# RGMII_ETH_PHY.net
KiCad netlist of a schematic drawn in Altium Designer
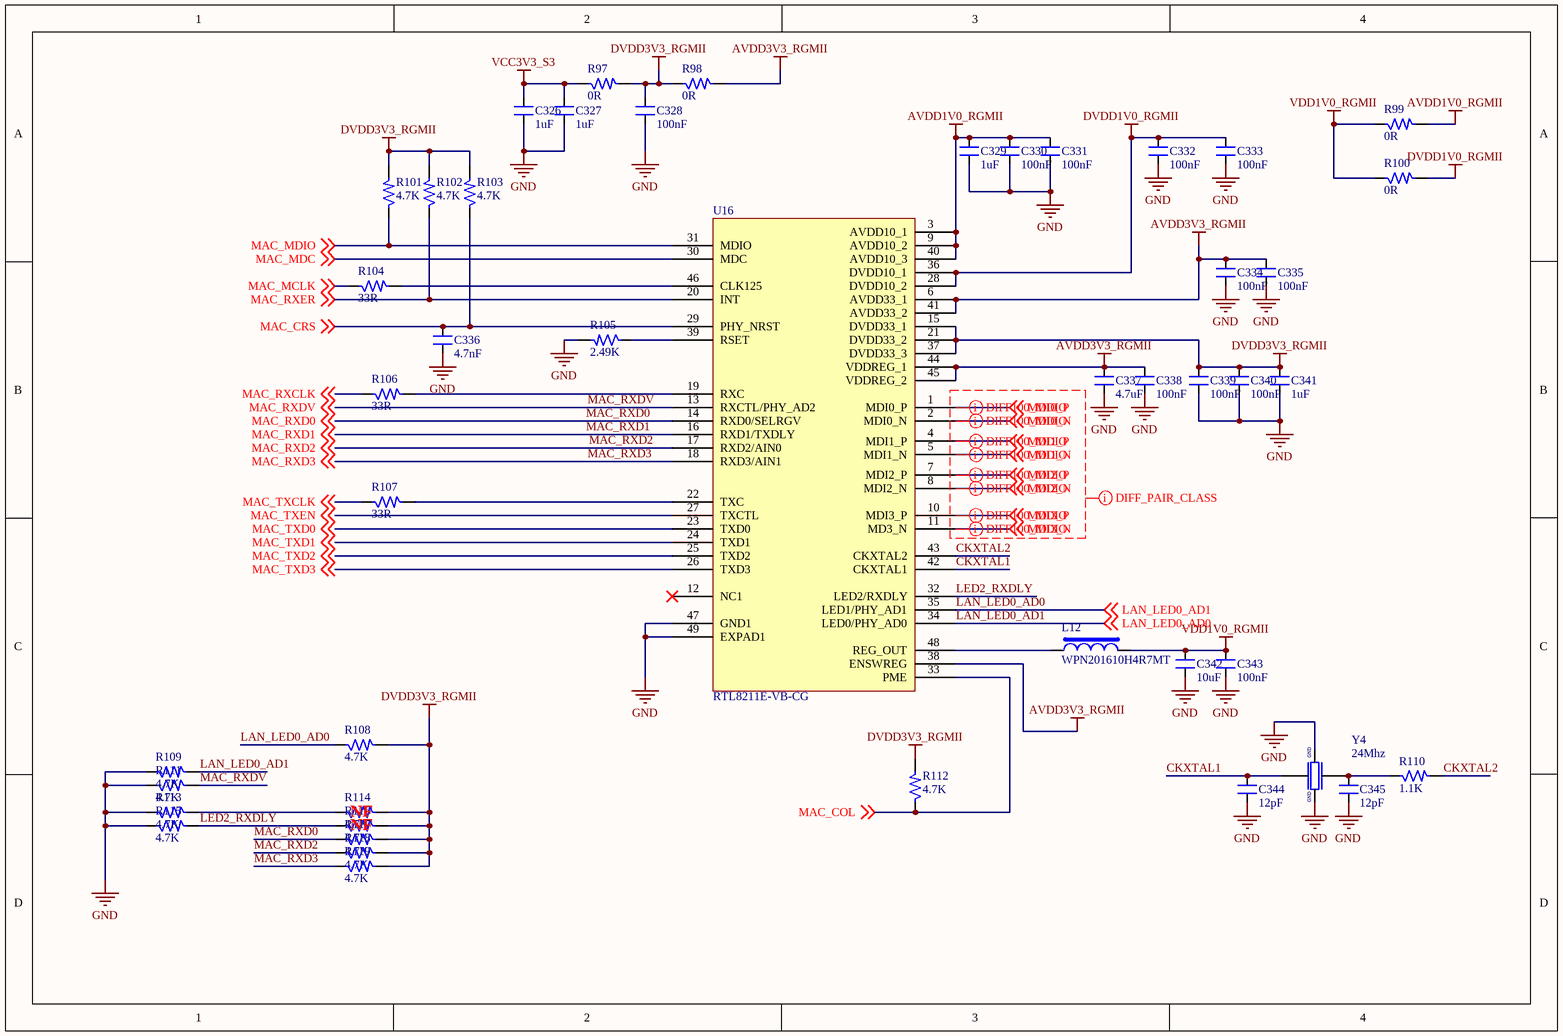
[diagram p0: RGMII ETH PHY.SchDoc]

(export (version "E")
  (design (tool "Eeschema 10.0.6"))
  (components
    (comp (ref "C326")
      (value "1uF")
      (footprint "CAP_0603")
      (description "1µF ±10% 10V Ceramic Capacitor X5R 0603 (1608 Metric)")
      (fields
        (field (name "MANUFACTURER") "Samsung Electro-Mechanics")
        (field (name "MANUFACTURER PART NUMBER") "CL10A105KP8NNNC")
      )
      (libsource (lib "RK3399 _Module_Schlib") (part "CAP_1uF-10V-5%-0603"))
    )
    (comp (ref "C327")
      (value "1uF")
      (footprint "CAP_0603")
      (description "1µF ±10% 10V Ceramic Capacitor X5R 0603 (1608 Metric)")
      (fields
        (field (name "MANUFACTURER") "Samsung Electro-Mechanics")
        (field (name "MANUFACTURER PART NUMBER") "CL10A105KP8NNNC")
      )
      (libsource (lib "RK3399 _Module_Schlib") (part "CAP_1uF-10V-5%-0603"))
    )
    (comp (ref "C328")
      (value "100nF")
      (footprint "CAP_0603")
      (description "0.1µF ±10% 10V Ceramic Capacitor X7R 0603 (1608 Metric)")
      (fields
        (field (name "MANUFACTURER") "Yageo")
        (field (name "MANUFACTURER PART NUMBER") "CC0603KRX7R6BB104")
      )
      (libsource (lib "RK3399 _Module_Schlib") (part "CAP_100nF-10V-5%-0603"))
    )
    (comp (ref "C329")
      (value "1uF")
      (footprint "CAP_0603")
      (description "1µF ±10% 10V Ceramic Capacitor X5R 0603 (1608 Metric)")
      (fields
        (field (name "MANUFACTURER") "Samsung Electro-Mechanics")
        (field (name "MANUFACTURER PART NUMBER") "CL10A105KP8NNNC")
      )
      (libsource (lib "RK3399 _Module_Schlib") (part "CAP_1uF-10V-5%-0603"))
    )
    (comp (ref "C330")
      (value "100nF")
      (footprint "CAP_0603")
      (description "0.1µF ±10% 10V Ceramic Capacitor X7R 0603 (1608 Metric)")
      (fields
        (field (name "MANUFACTURER") "Yageo")
        (field (name "MANUFACTURER PART NUMBER") "CC0603KRX7R6BB104")
      )
      (libsource (lib "RK3399 _Module_Schlib") (part "CAP_100nF-10V-5%-0603"))
    )
    (comp (ref "C331")
      (value "100nF")
      (footprint "CAP_0603")
      (description "0.1µF ±10% 10V Ceramic Capacitor X7R 0603 (1608 Metric)")
      (fields
        (field (name "MANUFACTURER") "Yageo")
        (field (name "MANUFACTURER PART NUMBER") "CC0603KRX7R6BB104")
      )
      (libsource (lib "RK3399 _Module_Schlib") (part "CAP_100nF-10V-5%-0603"))
    )
    (comp (ref "C332")
      (value "100nF")
      (footprint "CAP_0603")
      (description "0.1µF ±10% 10V Ceramic Capacitor X7R 0603 (1608 Metric)")
      (fields
        (field (name "MANUFACTURER") "Yageo")
        (field (name "MANUFACTURER PART NUMBER") "CC0603KRX7R6BB104")
      )
      (libsource (lib "RK3399 _Module_Schlib") (part "CAP_100nF-10V-5%-0603"))
    )
    (comp (ref "C333")
      (value "100nF")
      (footprint "CAP_0603")
      (description "0.1µF ±10% 10V Ceramic Capacitor X7R 0603 (1608 Metric)")
      (fields
        (field (name "MANUFACTURER") "Yageo")
        (field (name "MANUFACTURER PART NUMBER") "CC0603KRX7R6BB104")
      )
      (libsource (lib "RK3399 _Module_Schlib") (part "CAP_100nF-10V-5%-0603"))
    )
    (comp (ref "C334")
      (value "100nF")
      (footprint "CAP_0603")
      (description "0.1µF ±10% 10V Ceramic Capacitor X7R 0603 (1608 Metric)")
      (fields
        (field (name "MANUFACTURER") "Yageo")
        (field (name "MANUFACTURER PART NUMBER") "CC0603KRX7R6BB104")
      )
      (libsource (lib "RK3399 _Module_Schlib") (part "CAP_100nF-10V-5%-0603"))
    )
    (comp (ref "C335")
      (value "100nF")
      (footprint "CAP_0603")
      (description "0.1µF ±10% 10V Ceramic Capacitor X7R 0603 (1608 Metric)")
      (fields
        (field (name "MANUFACTURER") "Yageo")
        (field (name "MANUFACTURER PART NUMBER") "CC0603KRX7R6BB104")
      )
      (libsource (lib "RK3399 _Module_Schlib") (part "CAP_100nF-10V-5%-0603"))
    )
    (comp (ref "C336")
      (value "4.7nF")
      (footprint "CAP_0603")
      (description "4700pF ±10% 10V Ceramic Capacitor X7R 0603 (1608 Metric)")
      (fields
        (field (name "MANUFACTURER") "KEMET")
        (field (name "MANUFACTURER PART NUMBER") "C0603C472K8RACTU")
      )
      (libsource (lib "RK3399 _Module_Schlib") (part "CAP_4.7nF-10V-10%-0603"))
    )
    (comp (ref "C337")
      (value "4.7uF")
      (footprint "CAP_0603")
      (description "4.7µF ±10% 16V Ceramic Capacitor X5R 0603 (1608 Metric)")
      (fields
        (field (name "MANUFACTURER") "Murata Electronics")
        (field (name "MANUFACTURER PART NUMBER") "GRM188R61C475KAAJD")
      )
      (libsource (lib "RK3399 _Module_Schlib") (part "CAP_4.7uF-16V-10%-0603"))
    )
    (comp (ref "C338")
      (value "100nF")
      (footprint "CAP_0603")
      (description "0.1µF ±10% 10V Ceramic Capacitor X7R 0603 (1608 Metric)")
      (fields
        (field (name "MANUFACTURER") "Yageo")
        (field (name "MANUFACTURER PART NUMBER") "CC0603KRX7R6BB104")
      )
      (libsource (lib "RK3399 _Module_Schlib") (part "CAP_100nF-10V-5%-0603"))
    )
    (comp (ref "C339")
      (value "100nF")
      (footprint "CAP_0603")
      (description "0.1µF ±10% 10V Ceramic Capacitor X7R 0603 (1608 Metric)")
      (fields
        (field (name "MANUFACTURER") "Yageo")
        (field (name "MANUFACTURER PART NUMBER") "CC0603KRX7R6BB104")
      )
      (libsource (lib "RK3399 _Module_Schlib") (part "CAP_100nF-10V-5%-0603"))
    )
    (comp (ref "C340")
      (value "100nF")
      (footprint "CAP_0603")
      (description "0.1µF ±10% 10V Ceramic Capacitor X7R 0603 (1608 Metric)")
      (fields
        (field (name "MANUFACTURER") "Yageo")
        (field (name "MANUFACTURER PART NUMBER") "CC0603KRX7R6BB104")
      )
      (libsource (lib "RK3399 _Module_Schlib") (part "CAP_100nF-10V-5%-0603"))
    )
    (comp (ref "C341")
      (value "1uF")
      (footprint "CAP_0603")
      (description "1µF ±10% 10V Ceramic Capacitor X5R 0603 (1608 Metric)")
      (fields
        (field (name "MANUFACTURER") "Samsung Electro-Mechanics")
        (field (name "MANUFACTURER PART NUMBER") "CL10A105KP8NNNC")
      )
      (libsource (lib "RK3399 _Module_Schlib") (part "CAP_1uF-10V-5%-0603"))
    )
    (comp (ref "C342")
      (value "10uF")
      (footprint "CAP_0603")
      (description "10µF ±10% 10V Ceramic Capacitor X5R 0603 (1608 Metric)")
      (fields
        (field (name "MANUFACTURER PART NUMBER") "GRM188R61A106KE69J")
        (field (name "MANUFACTURER") "Murata Electronics")
      )
      (libsource (lib "RK3399 _Module_Schlib") (part "CAP_10uF-10V-10%-0603"))
    )
    (comp (ref "C343")
      (value "100nF")
      (footprint "CAP_0603")
      (description "0.1µF ±10% 10V Ceramic Capacitor X7R 0603 (1608 Metric)")
      (fields
        (field (name "MANUFACTURER") "Yageo")
        (field (name "MANUFACTURER PART NUMBER") "CC0603KRX7R6BB104")
      )
      (libsource (lib "RK3399 _Module_Schlib") (part "CAP_100nF-10V-5%-0603"))
    )
    (comp (ref "C344")
      (value "12pF")
      (footprint "CAP_0603")
      (description "12pF ±10% 10V Ceramic Capacitor X8R 0603 (1608 Metric)")
      (fields
        (field (name "MANUFACTURER") "KEMET")
        (field (name "MANUFACTURER PART NUMBER") "C0603X120K8HAC7867")
      )
      (libsource (lib "RK3399 _Module_Schlib") (part "CAP_12pF-10V-10%-0603"))
    )
    (comp (ref "C345")
      (value "12pF")
      (footprint "CAP_0603")
      (description "12pF ±10% 10V Ceramic Capacitor X8R 0603 (1608 Metric)")
      (fields
        (field (name "MANUFACTURER") "KEMET")
        (field (name "MANUFACTURER PART NUMBER") "C0603X120K8HAC7867")
      )
      (libsource (lib "RK3399 _Module_Schlib") (part "CAP_12pF-10V-10%-0603"))
    )
    (comp (ref "L12")
      (value "WPN201610H4R7MT")
      (footprint "IND_62.9_110X86.6_SMD")
      (description "4.7uH ±20% 900mA 425mΩ SMD,2.0x1.6x1.0mm Power Inductors RoHS")
      (fields (field (name "MANUFACTURER") "Sunlord"))
      (libsource (lib "RK3399 _Module_Schlib") (part "IND_4.7uH-0.9A-20%-SMD"))
    )
    (comp (ref "R97")
      (value "0R")
      (footprint "RES_0603")
      (description "0 Ohms Jumper 0.1W, 1/10W Chip Resistor 0603 (1608 Metric) Thick Film")
      (fields
        (field (name "MANUFACTURER") "Yageo")
        (field (name "MANUFACTURER PART NUMBER") "RC0603JR-070RL")
      )
      (libsource (lib "RK3399 _Module_Schlib") (part "RES_0R-0.1W-1%-0603"))
    )
    (comp (ref "R98")
      (value "0R")
      (footprint "RES_0603")
      (description "0 Ohms Jumper 0.1W, 1/10W Chip Resistor 0603 (1608 Metric) Thick Film")
      (fields
        (field (name "MANUFACTURER") "Yageo")
        (field (name "MANUFACTURER PART NUMBER") "RC0603JR-070RL")
      )
      (libsource (lib "RK3399 _Module_Schlib") (part "RES_0R-0.1W-1%-0603"))
    )
    (comp (ref "R99")
      (value "0R")
      (footprint "RES_0603")
      (description "0 Ohms Jumper 0.1W, 1/10W Chip Resistor 0603 (1608 Metric) Thick Film")
      (fields
        (field (name "MANUFACTURER") "Yageo")
        (field (name "MANUFACTURER PART NUMBER") "RC0603JR-070RL")
      )
      (libsource (lib "RK3399 _Module_Schlib") (part "RES_0R-0.1W-1%-0603"))
    )
    (comp (ref "R100")
      (value "0R")
      (footprint "RES_0603")
      (description "0 Ohms Jumper 0.1W, 1/10W Chip Resistor 0603 (1608 Metric) Thick Film")
      (fields
        (field (name "MANUFACTURER") "Yageo")
        (field (name "MANUFACTURER PART NUMBER") "RC0603JR-070RL")
      )
      (libsource (lib "RK3399 _Module_Schlib") (part "RES_0R-0.1W-1%-0603"))
    )
    (comp (ref "R101")
      (value "4.7K")
      (footprint "RES_0603")
      (fields
        (field (name "MANUFACTURER") "TE Connectivity Passive Product")
        (field (name "MANUFACTURER PART NUMBER") "CRGCQ0603F4K7")
      )
      (libsource (lib "RK3399 _Module_Schlib") (part "RES_4.7K-0.1W-1%-0603"))
    )
    (comp (ref "R102")
      (value "4.7K")
      (footprint "RES_0603")
      (fields
        (field (name "MANUFACTURER") "TE Connectivity Passive Product")
        (field (name "MANUFACTURER PART NUMBER") "CRGCQ0603F4K7")
      )
      (libsource (lib "RK3399 _Module_Schlib") (part "RES_4.7K-0.1W-1%-0603"))
    )
    (comp (ref "R103")
      (value "4.7K")
      (footprint "RES_0603")
      (fields
        (field (name "MANUFACTURER") "TE Connectivity Passive Product")
        (field (name "MANUFACTURER PART NUMBER") "CRGCQ0603F4K7")
      )
      (libsource (lib "RK3399 _Module_Schlib") (part "RES_4.7K-0.1W-1%-0603"))
    )
    (comp (ref "R104")
      (value "33R")
      (footprint "RES_0402")
      (description "33 Ohms ±1% 0.1W, 1/10W Chip Resistor 0402 (1005 Metric) Automotive AEC-Q200 Thick Film")
      (fields
        (field (name "MANUFACTURER") "Panasonic Electronic Components")
        (field (name "MANUFACTURER PART NUMBER") "ERJ-2RKF33R0X")
      )
      (libsource (lib "RK3399 _Module_Schlib") (part "RES_33R-0.1W-1%-0402"))
    )
    (comp (ref "R105")
      (value "2.49K")
      (footprint "RES_0603")
      (description "2.49 kOhms ±1% 0.1W, 1/10W Chip Resistor 0603 (1608 Metric) Automotive AEC-Q200 Thick Film")
      (fields
        (field (name "MANUFACTURER") "Stackpole Electronics Inc")
        (field (name "MANUFACTURER PART NUMBER") "RMCF0603FT2K49")
      )
      (libsource (lib "RK3399 _Module_Schlib") (part "RES_2.49K-0.1W-1%-0603"))
    )
    (comp (ref "R106")
      (value "33R")
      (footprint "RES_0402")
      (description "33 Ohms ±1% 0.1W, 1/10W Chip Resistor 0402 (1005 Metric) Automotive AEC-Q200 Thick Film")
      (fields
        (field (name "MANUFACTURER") "Panasonic Electronic Components")
        (field (name "MANUFACTURER PART NUMBER") "ERJ-2RKF33R0X")
      )
      (libsource (lib "RK3399 _Module_Schlib") (part "RES_33R-0.1W-1%-0402"))
    )
    (comp (ref "R107")
      (value "33R")
      (footprint "RES_0402")
      (description "33 Ohms ±1% 0.1W, 1/10W Chip Resistor 0402 (1005 Metric) Automotive AEC-Q200 Thick Film")
      (fields
        (field (name "MANUFACTURER") "Panasonic Electronic Components")
        (field (name "MANUFACTURER PART NUMBER") "ERJ-2RKF33R0X")
      )
      (libsource (lib "RK3399 _Module_Schlib") (part "RES_33R-0.1W-1%-0402"))
    )
    (comp (ref "R108")
      (value "4.7K")
      (footprint "RES_0603")
      (fields
        (field (name "MANUFACTURER") "TE Connectivity Passive Product")
        (field (name "MANUFACTURER PART NUMBER") "CRGCQ0603F4K7")
      )
      (libsource (lib "RK3399 _Module_Schlib") (part "RES_4.7K-0.1W-1%-0603"))
    )
    (comp (ref "R109")
      (value "4.7K")
      (footprint "RES_0603")
      (fields
        (field (name "MANUFACTURER") "TE Connectivity Passive Product")
        (field (name "MANUFACTURER PART NUMBER") "CRGCQ0603F4K7")
      )
      (libsource (lib "RK3399 _Module_Schlib") (part "RES_4.7K-0.1W-1%-0603"))
    )
    (comp (ref "R110")
      (value "1.1K")
      (footprint "RES_0603")
      (description "47 kOhms ±1% 0.1W, 1/10W Chip Resistor 0603 (1608 Metric) Thick Film")
      (fields
        (field (name "MANUFACTURER") "Yageo")
        (field (name "MANUFACTURER PART NUMBER") "RC0603FR-0747KL")
      )
      (libsource (lib "RK3399 _Module_Schlib") (part "RES_1.1K-0.1W-1%-0603"))
    )
    (comp (ref "R111")
      (value "4.7K")
      (footprint "RES_0603")
      (fields
        (field (name "MANUFACTURER") "TE Connectivity Passive Product")
        (field (name "MANUFACTURER PART NUMBER") "CRGCQ0603F4K7")
      )
      (libsource (lib "RK3399 _Module_Schlib") (part "RES_4.7K-0.1W-1%-0603"))
    )
    (comp (ref "R112")
      (value "4.7K")
      (footprint "RES_0603")
      (fields
        (field (name "MANUFACTURER") "TE Connectivity Passive Product")
        (field (name "MANUFACTURER PART NUMBER") "CRGCQ0603F4K7")
      )
      (libsource (lib "RK3399 _Module_Schlib") (part "RES_4.7K-0.1W-1%-0603"))
    )
    (comp (ref "R113")
      (value "4.7K")
      (footprint "RES_0603")
      (fields
        (field (name "MANUFACTURER") "TE Connectivity Passive Product")
        (field (name "MANUFACTURER PART NUMBER") "CRGCQ0603F4K7")
      )
      (libsource (lib "RK3399 _Module_Schlib") (part "RES_4.7K-0.1W-1%-0603"))
    )
    (comp (ref "R114")
      (value "4.7K")
      (footprint "RES_0603")
      (fields
        (field (name "MANUFACTURER") "TE Connectivity Passive Product")
        (field (name "MANUFACTURER PART NUMBER") "CRGCQ0603F4K7")
      )
      (libsource (lib "RK3399 _Module_Schlib") (part "RES_4.7K-0.1W-1%-0603"))
    )
    (comp (ref "R115")
      (value "4.7K")
      (footprint "RES_0603")
      (fields
        (field (name "MANUFACTURER") "TE Connectivity Passive Product")
        (field (name "MANUFACTURER PART NUMBER") "CRGCQ0603F4K7")
      )
      (libsource (lib "RK3399 _Module_Schlib") (part "RES_4.7K-0.1W-1%-0603"))
    )
    (comp (ref "R116")
      (value "4.7K")
      (footprint "RES_0603")
      (fields
        (field (name "MANUFACTURER") "TE Connectivity Passive Product")
        (field (name "MANUFACTURER PART NUMBER") "CRGCQ0603F4K7")
      )
      (libsource (lib "RK3399 _Module_Schlib") (part "RES_4.7K-0.1W-1%-0603"))
    )
    (comp (ref "R117")
      (value "4.7K")
      (footprint "RES_0603")
      (fields
        (field (name "MANUFACTURER") "TE Connectivity Passive Product")
        (field (name "MANUFACTURER PART NUMBER") "CRGCQ0603F4K7")
      )
      (libsource (lib "RK3399 _Module_Schlib") (part "RES_4.7K-0.1W-1%-0603"))
    )
    (comp (ref "R118")
      (value "4.7K")
      (footprint "RES_0603")
      (fields
        (field (name "MANUFACTURER") "TE Connectivity Passive Product")
        (field (name "MANUFACTURER PART NUMBER") "CRGCQ0603F4K7")
      )
      (libsource (lib "RK3399 _Module_Schlib") (part "RES_4.7K-0.1W-1%-0603"))
    )
    (comp (ref "R119")
      (value "4.7K")
      (footprint "RES_0603")
      (fields
        (field (name "MANUFACTURER") "TE Connectivity Passive Product")
        (field (name "MANUFACTURER PART NUMBER") "CRGCQ0603F4K7")
      )
      (libsource (lib "RK3399 _Module_Schlib") (part "RES_4.7K-0.1W-1%-0603"))
    )
    (comp (ref "U16")
      (value "RTL8211E-VB-CG")
      (footprint "QFN48_19.6_324X324_SMD")
      (fields (field (name "MANUFACTURER") "Realtek Semicon"))
      (libsource (lib "RK3399 _Module_Schlib") (part "IC_RTL8211E-VB-CG"))
    )
    (comp (ref "Y4")
      (value "24Mhz")
      (footprint "XTAL_ABM8AIG-24.000MHZ-12-2Z-T3")
      (description "24MHz ±20ppm Crystal 12pF 50 Ohms 4-SMD, No Lead")
      (fields
        (field (name "MANUFACTURER") "Abracon LLC")
        (field (name "MANUFACTURER PART NUMBER") "ABM8AIG-24.000MHZ-12-2Z-T3")
      )
      (libsource (lib "RK3399 _Module_Schlib") (part "XTAL_24Mhz-12pF-4-SMD"))
    )
  )
  (nets
    (net (code "1") (name "/CKXTAL1") (class "Default")
      (node (ref "C344") (pin "2") (pinfunction "2_2") (pintype "passive"))
      (node (ref "U16") (pin "42") (pinfunction "CKXTAL1_42") (pintype "passive"))
      (node (ref "Y4") (pin "1") (pinfunction "1_1") (pintype "passive"))
    )
    (net (code "2") (name "/CKXTAL2") (class "Default")
      (node (ref "R110") (pin "2") (pinfunction "2_2") (pintype "passive"))
      (node (ref "U16") (pin "43") (pinfunction "CKXTAL2_43") (pintype "passive"))
    )
    (net (code "3") (name "/LED2_RXDLY") (class "Default")
      (node (ref "R115") (pin "2") (pinfunction "2_2") (pintype "passive"))
      (node (ref "R116") (pin "1") (pinfunction "1_1") (pintype "passive"))
      (node (ref "U16") (pin "32") (pinfunction "LED2/RXDLY_32") (pintype "passive"))
    )
    (net (code "4") (name "AVDD1V0_RGMII") (class "Default")
      (node (ref "C329") (pin "2") (pinfunction "2_2") (pintype "passive"))
      (node (ref "C330") (pin "2") (pinfunction "2_2") (pintype "passive"))
      (node (ref "C331") (pin "2") (pinfunction "2_2") (pintype "passive"))
      (node (ref "R99") (pin "2") (pinfunction "2_2") (pintype "passive"))
      (node (ref "U16") (pin "3") (pinfunction "AVDD10_1_3") (pintype "passive"))
      (node (ref "U16") (pin "40") (pinfunction "AVDD10_3_40") (pintype "passive"))
      (node (ref "U16") (pin "9") (pinfunction "AVDD10_2_9") (pintype "passive"))
    )
    (net (code "5") (name "AVDD3V3_RGMII") (class "Default")
      (node (ref "C334") (pin "2") (pinfunction "2_2") (pintype "passive"))
      (node (ref "C335") (pin "2") (pinfunction "2_2") (pintype "passive"))
      (node (ref "C337") (pin "2") (pinfunction "2_2") (pintype "passive"))
      (node (ref "C338") (pin "2") (pinfunction "2_2") (pintype "passive"))
      (node (ref "R98") (pin "2") (pinfunction "2_2") (pintype "passive"))
      (node (ref "U16") (pin "38") (pinfunction "ENSWREG_38") (pintype "passive"))
      (node (ref "U16") (pin "41") (pinfunction "AVDD33_2_41") (pintype "passive"))
      (node (ref "U16") (pin "44") (pinfunction "VDDREG_1_44") (pintype "passive"))
      (node (ref "U16") (pin "45") (pinfunction "VDDREG_2_45") (pintype "passive"))
      (node (ref "U16") (pin "6") (pinfunction "AVDD33_1_6") (pintype "passive"))
    )
    (net (code "6") (name "DVDD1V0_RGMII") (class "Default")
      (node (ref "C332") (pin "2") (pinfunction "2_2") (pintype "passive"))
      (node (ref "C333") (pin "2") (pinfunction "2_2") (pintype "passive"))
      (node (ref "R100") (pin "2") (pinfunction "2_2") (pintype "passive"))
      (node (ref "U16") (pin "28") (pinfunction "DVDD10_2_28") (pintype "passive"))
      (node (ref "U16") (pin "36") (pinfunction "DVDD10_1_36") (pintype "passive"))
    )
    (net (code "7") (name "DVDD3V3_RGMII") (class "Default")
      (node (ref "C328") (pin "2") (pinfunction "2_2") (pintype "passive"))
      (node (ref "C339") (pin "2") (pinfunction "2_2") (pintype "passive"))
      (node (ref "C340") (pin "2") (pinfunction "2_2") (pintype "passive"))
      (node (ref "C341") (pin "2") (pinfunction "2_2") (pintype "passive"))
      (node (ref "R101") (pin "2") (pinfunction "2_2") (pintype "passive"))
      (node (ref "R102") (pin "2") (pinfunction "2_2") (pintype "passive"))
      (node (ref "R103") (pin "2") (pinfunction "2_2") (pintype "passive"))
      (node (ref "R108") (pin "2") (pinfunction "2_2") (pintype "passive"))
      (node (ref "R112") (pin "2") (pinfunction "2_2") (pintype "passive"))
      (node (ref "R114") (pin "2") (pinfunction "2_2") (pintype "passive"))
      (node (ref "R116") (pin "2") (pinfunction "2_2") (pintype "passive"))
      (node (ref "R117") (pin "2") (pinfunction "2_2") (pintype "passive"))
      (node (ref "R118") (pin "2") (pinfunction "2_2") (pintype "passive"))
      (node (ref "R119") (pin "2") (pinfunction "2_2") (pintype "passive"))
      (node (ref "R97") (pin "2") (pinfunction "2_2") (pintype "passive"))
      (node (ref "R98") (pin "1") (pinfunction "1_1") (pintype "passive"))
      (node (ref "U16") (pin "15") (pinfunction "DVDD33_1_15") (pintype "passive"))
      (node (ref "U16") (pin "21") (pinfunction "DVDD33_2_21") (pintype "passive"))
      (node (ref "U16") (pin "37") (pinfunction "DVDD33_3_37") (pintype "passive"))
    )
    (net (code "8") (name "GND") (class "Default")
      (node (ref "C326") (pin "1") (pinfunction "1_1") (pintype "passive"))
      (node (ref "C327") (pin "1") (pinfunction "1_1") (pintype "passive"))
      (node (ref "C328") (pin "1") (pinfunction "1_1") (pintype "passive"))
      (node (ref "C329") (pin "1") (pinfunction "1_1") (pintype "passive"))
      (node (ref "C330") (pin "1") (pinfunction "1_1") (pintype "passive"))
      (node (ref "C331") (pin "1") (pinfunction "1_1") (pintype "passive"))
      (node (ref "C332") (pin "1") (pinfunction "1_1") (pintype "passive"))
      (node (ref "C333") (pin "1") (pinfunction "1_1") (pintype "passive"))
      (node (ref "C334") (pin "1") (pinfunction "1_1") (pintype "passive"))
      (node (ref "C335") (pin "1") (pinfunction "1_1") (pintype "passive"))
      (node (ref "C336") (pin "1") (pinfunction "1_1") (pintype "passive"))
      (node (ref "C337") (pin "1") (pinfunction "1_1") (pintype "passive"))
      (node (ref "C338") (pin "1") (pinfunction "1_1") (pintype "passive"))
      (node (ref "C339") (pin "1") (pinfunction "1_1") (pintype "passive"))
      (node (ref "C340") (pin "1") (pinfunction "1_1") (pintype "passive"))
      (node (ref "C341") (pin "1") (pinfunction "1_1") (pintype "passive"))
      (node (ref "C342") (pin "1") (pinfunction "1_1") (pintype "passive"))
      (node (ref "C343") (pin "1") (pinfunction "1_1") (pintype "passive"))
      (node (ref "C344") (pin "1") (pinfunction "1_1") (pintype "passive"))
      (node (ref "C345") (pin "1") (pinfunction "1_1") (pintype "passive"))
      (node (ref "R105") (pin "2") (pinfunction "2_2") (pintype "passive"))
      (node (ref "R109") (pin "1") (pinfunction "1_1") (pintype "passive"))
      (node (ref "R111") (pin "1") (pinfunction "1_1") (pintype "passive"))
      (node (ref "R113") (pin "1") (pinfunction "1_1") (pintype "passive"))
      (node (ref "R115") (pin "1") (pinfunction "1_1") (pintype "passive"))
      (node (ref "U16") (pin "47") (pinfunction "GND1_47") (pintype "passive"))
      (node (ref "U16") (pin "49") (pinfunction "EXPAD1_49") (pintype "passive"))
      (node (ref "Y4") (pin "2") (pinfunction "2_2") (pintype "passive"))
      (node (ref "Y4") (pin "4") (pinfunction "4_4") (pintype "passive"))
    )
    (net (code "9") (name "LAN_LED0_AD0") (class "Default")
      (node (ref "R108") (pin "1") (pinfunction "1_1") (pintype "passive"))
      (node (ref "R109") (pin "2") (pinfunction "2_2") (pintype "passive"))
      (node (ref "U16") (pin "34") (pinfunction "LED0/PHY_AD0_34") (pintype "passive"))
      (node (ref "U16") (pin "35") (pinfunction "LED1/PHY_AD1_35") (pintype "passive"))
    )
    (net (code "10") (name "MAC_COL") (class "Default")
      (node (ref "R112") (pin "1") (pinfunction "1_1") (pintype "passive"))
      (node (ref "U16") (pin "33") (pinfunction "PME_33") (pintype "passive"))
    )
    (net (code "11") (name "MAC_CRS") (class "Default")
      (node (ref "C336") (pin "2") (pinfunction "2_2") (pintype "passive"))
      (node (ref "R103") (pin "1") (pinfunction "1_1") (pintype "passive"))
      (node (ref "U16") (pin "29") (pinfunction "PHY_NRST_29") (pintype "passive"))
    )
    (net (code "12") (name "MAC_MCLK") (class "Default")
      (node (ref "R104") (pin "1") (pinfunction "1_1") (pintype "passive"))
    )
    (net (code "13") (name "MAC_MDC") (class "Default")
      (node (ref "U16") (pin "30") (pinfunction "MDC_30") (pintype "passive"))
    )
    (net (code "14") (name "MAC_MDIO") (class "Default")
      (node (ref "R101") (pin "1") (pinfunction "1_1") (pintype "passive"))
      (node (ref "U16") (pin "31") (pinfunction "MDIO_31") (pintype "passive"))
    )
    (net (code "15") (name "MAC_RXCLK") (class "Default")
      (node (ref "R106") (pin "1") (pinfunction "1_1") (pintype "passive"))
    )
    (net (code "16") (name "MAC_RXD0") (class "Default")
      (node (ref "R117") (pin "1") (pinfunction "1_1") (pintype "passive"))
      (node (ref "U16") (pin "14") (pinfunction "RXD0/SELRGV_14") (pintype "passive"))
    )
    (net (code "17") (name "MAC_RXD1") (class "Default")
      (node (ref "U16") (pin "16") (pinfunction "RXD1/TXDLY_16") (pintype "passive"))
    )
    (net (code "18") (name "MAC_RXD2") (class "Default")
      (node (ref "R118") (pin "1") (pinfunction "1_1") (pintype "passive"))
      (node (ref "U16") (pin "17") (pinfunction "RXD2/AIN0_17") (pintype "passive"))
    )
    (net (code "19") (name "MAC_RXD3") (class "Default")
      (node (ref "R119") (pin "1") (pinfunction "1_1") (pintype "passive"))
      (node (ref "U16") (pin "18") (pinfunction "RXD3/AIN1_18") (pintype "passive"))
    )
    (net (code "20") (name "MAC_RXDV") (class "Default")
      (node (ref "R111") (pin "2") (pinfunction "2_2") (pintype "passive"))
      (node (ref "U16") (pin "13") (pinfunction "RXCTL/PHY_AD2_13") (pintype "passive"))
    )
    (net (code "21") (name "MAC_RXER") (class "Default")
      (node (ref "R102") (pin "1") (pinfunction "1_1") (pintype "passive"))
      (node (ref "U16") (pin "20") (pinfunction "INT_20") (pintype "passive"))
    )
    (net (code "22") (name "MAC_TXCLK") (class "Default")
      (node (ref "R107") (pin "1") (pinfunction "1_1") (pintype "passive"))
    )
    (net (code "23") (name "MAC_TXD0") (class "Default")
      (node (ref "U16") (pin "23") (pinfunction "TXD0_23") (pintype "passive"))
    )
    (net (code "24") (name "MAC_TXD1") (class "Default")
      (node (ref "U16") (pin "24") (pinfunction "TXD1_24") (pintype "passive"))
    )
    (net (code "25") (name "MAC_TXD2") (class "Default")
      (node (ref "U16") (pin "25") (pinfunction "TXD2_25") (pintype "passive"))
    )
    (net (code "26") (name "MAC_TXD3") (class "Default")
      (node (ref "U16") (pin "26") (pinfunction "TXD3_26") (pintype "passive"))
    )
    (net (code "27") (name "MAC_TXEN") (class "Default")
      (node (ref "U16") (pin "27") (pinfunction "TXCTL_27") (pintype "passive"))
    )
    (net (code "28") (name "MDI0_N") (class "Default")
      (node (ref "U16") (pin "2") (pinfunction "MDI0_N_2") (pintype "passive"))
    )
    (net (code "29") (name "MDI0_P") (class "Default")
      (node (ref "U16") (pin "1") (pinfunction "MDI0_P_1") (pintype "passive"))
    )
    (net (code "30") (name "MDI1_N") (class "Default")
      (node (ref "U16") (pin "5") (pinfunction "MDI1_N_5") (pintype "passive"))
    )
    (net (code "31") (name "MDI1_P") (class "Default")
      (node (ref "U16") (pin "4") (pinfunction "MDI1_P_4") (pintype "passive"))
    )
    (net (code "32") (name "MDI2_N") (class "Default")
      (node (ref "U16") (pin "8") (pinfunction "MDI2_N_8") (pintype "passive"))
    )
    (net (code "33") (name "MDI2_P") (class "Default")
      (node (ref "U16") (pin "7") (pinfunction "MDI2_P_7") (pintype "passive"))
    )
    (net (code "34") (name "MDI3_N") (class "Default")
      (node (ref "U16") (pin "11") (pinfunction "MD3_N_11") (pintype "passive"))
    )
    (net (code "35") (name "MDI3_P") (class "Default")
      (node (ref "U16") (pin "10") (pinfunction "MDI3_P_10") (pintype "passive"))
    )
    (net (code "36") (name "Net-(C345-Pad2)") (class "Default")
      (node (ref "C345") (pin "2") (pinfunction "2_2") (pintype "passive"))
      (node (ref "R110") (pin "1") (pinfunction "1_1") (pintype "passive"))
      (node (ref "Y4") (pin "3") (pinfunction "3_3") (pintype "passive"))
    )
    (net (code "37") (name "Net-(R113-Pad2)") (class "Default")
      (node (ref "R113") (pin "2") (pinfunction "2_2") (pintype "passive"))
      (node (ref "R114") (pin "1") (pinfunction "1_1") (pintype "passive"))
    )
    (net (code "38") (name "Net-(U16-CLK125)") (class "Default")
      (node (ref "R104") (pin "2") (pinfunction "2_2") (pintype "passive"))
      (node (ref "U16") (pin "46") (pinfunction "CLK125_46") (pintype "passive"))
    )
    (net (code "39") (name "Net-(U16-REG_OUT)") (class "Default")
      (node (ref "L12") (pin "1") (pinfunction "1_1") (pintype "passive"))
      (node (ref "U16") (pin "48") (pinfunction "REG_OUT_48") (pintype "passive"))
    )
    (net (code "40") (name "Net-(U16-RSET)") (class "Default")
      (node (ref "R105") (pin "1") (pinfunction "1_1") (pintype "passive"))
      (node (ref "U16") (pin "39") (pinfunction "RSET_39") (pintype "passive"))
    )
    (net (code "41") (name "Net-(U16-RXC)") (class "Default")
      (node (ref "R106") (pin "2") (pinfunction "2_2") (pintype "passive"))
      (node (ref "U16") (pin "19") (pinfunction "RXC_19") (pintype "passive"))
    )
    (net (code "42") (name "Net-(U16-TXC)") (class "Default")
      (node (ref "R107") (pin "2") (pinfunction "2_2") (pintype "passive"))
      (node (ref "U16") (pin "22") (pinfunction "TXC_22") (pintype "passive"))
    )
    (net (code "43") (name "VCC3V3_S3") (class "Default")
      (node (ref "C326") (pin "2") (pinfunction "2_2") (pintype "passive"))
      (node (ref "C327") (pin "2") (pinfunction "2_2") (pintype "passive"))
      (node (ref "R97") (pin "1") (pinfunction "1_1") (pintype "passive"))
    )
    (net (code "44") (name "VDD1V0_RGMII") (class "Default")
      (node (ref "C342") (pin "2") (pinfunction "2_2") (pintype "passive"))
      (node (ref "C343") (pin "2") (pinfunction "2_2") (pintype "passive"))
      (node (ref "L12") (pin "2") (pinfunction "2_2") (pintype "passive"))
      (node (ref "R100") (pin "1") (pinfunction "1_1") (pintype "passive"))
      (node (ref "R99") (pin "1") (pinfunction "1_1") (pintype "passive"))
    )
    (net (code "45") (name "unconnected-(U16-NC1-Pad12)") (class "Default")
      (node (ref "U16") (pin "12") (pinfunction "NC1_12") (pintype "passive+no_connect"))
    )
  )
)
